# ch559.net
KiCad netlist of a schematic drawn in EAGLE
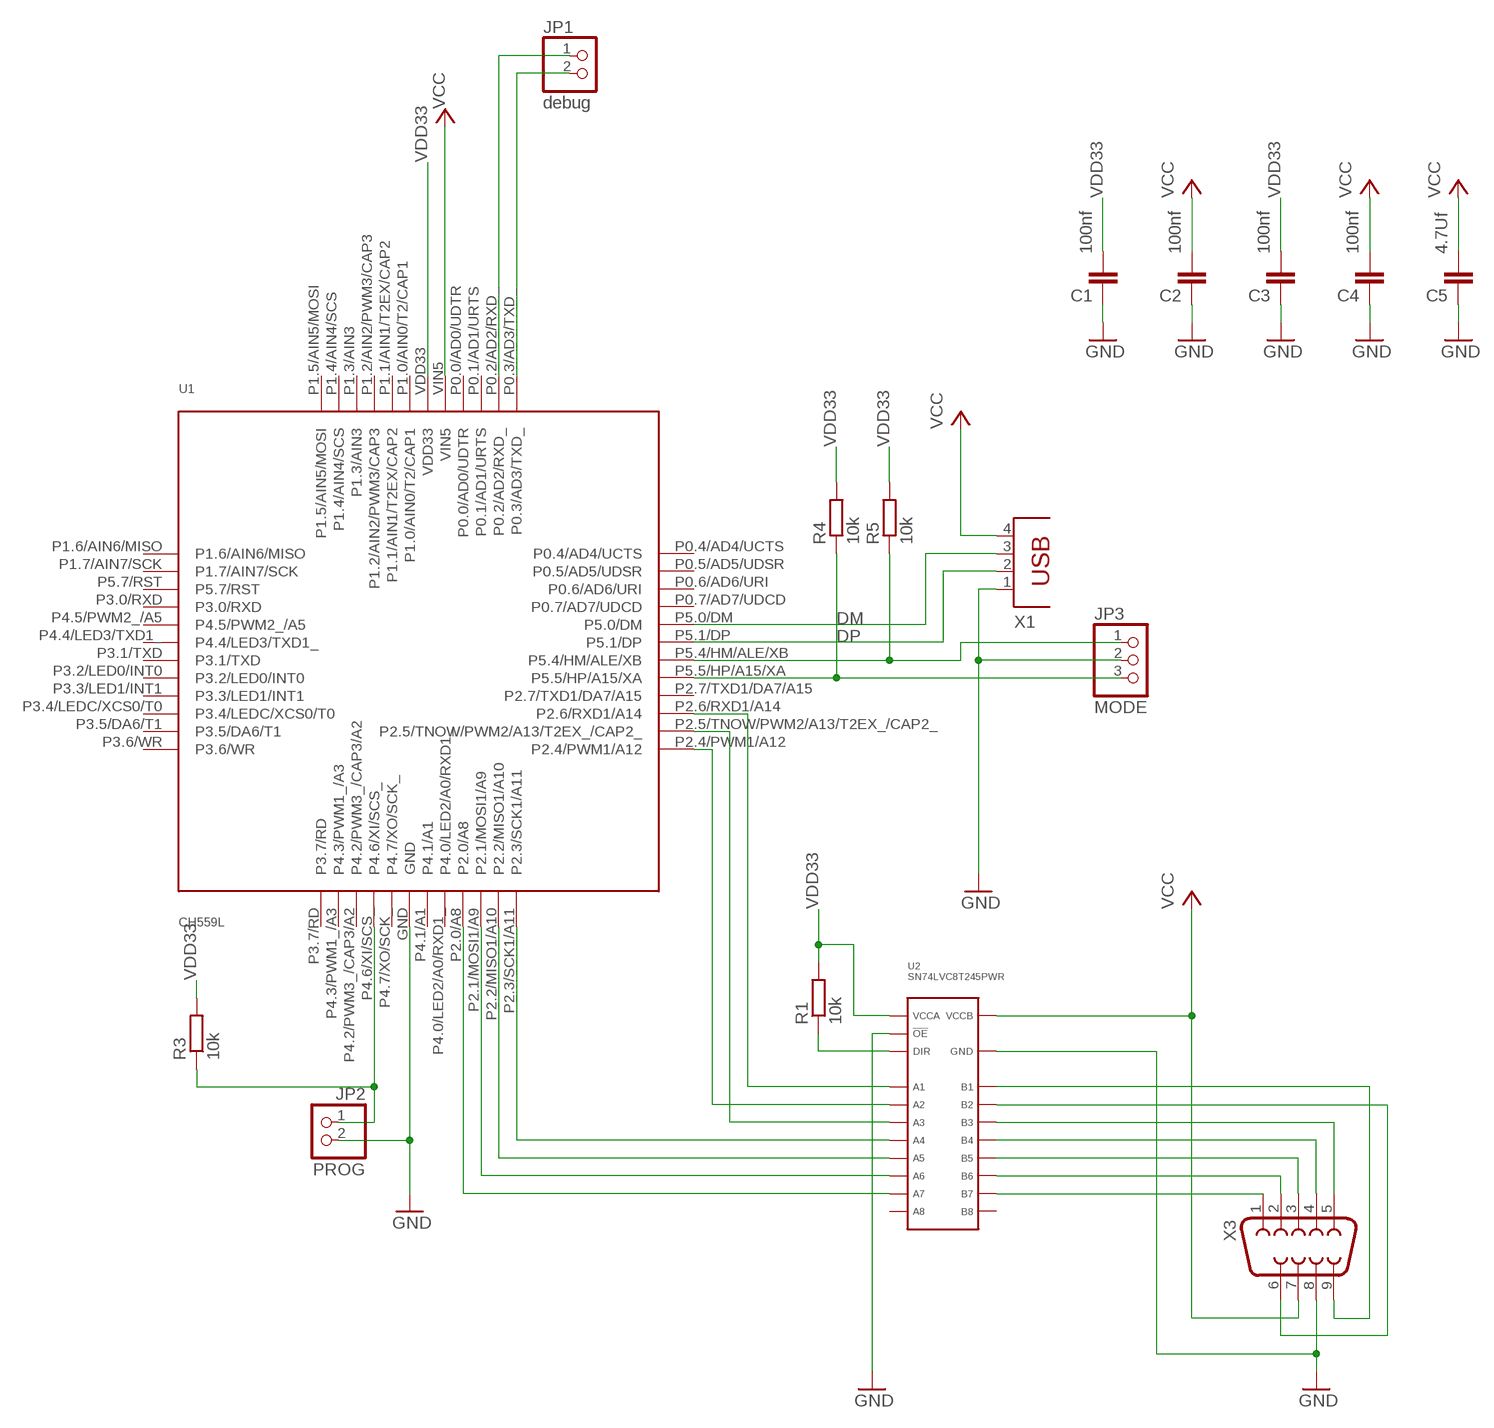
[diagram p0: schematic, sheet 1]

(export (version "E")
  (design (tool "Eeschema 10.0.6"))
  (components
    (comp (ref "C1")
      (value "100nf")
      (footprint "eagle-import:C0603")
      (libsource (lib "eagle-import") (part "C-EUC0603"))
    )
    (comp (ref "C2")
      (value "100nf")
      (footprint "eagle-import:C0603")
      (libsource (lib "eagle-import") (part "C-EUC0603"))
    )
    (comp (ref "C3")
      (value "100nf")
      (footprint "eagle-import:C0603")
      (libsource (lib "eagle-import") (part "C-EUC0603"))
    )
    (comp (ref "C4")
      (value "100nf")
      (footprint "eagle-import:C0603")
      (libsource (lib "eagle-import") (part "C-EUC0603"))
    )
    (comp (ref "C5")
      (value "4.7Uf")
      (footprint "eagle-import:C0603")
      (libsource (lib "eagle-import") (part "C-EUC0603"))
    )
    (comp (ref "JP1")
      (value "debug")
      (footprint "eagle-import:1X02")
      (libsource (lib "eagle-import") (part "pinhead_325_PINHD-1X2"))
    )
    (comp (ref "JP2")
      (value "PROG")
      (footprint "eagle-import:1X02")
      (libsource (lib "eagle-import") (part "PINHD-1X2"))
    )
    (comp (ref "JP3")
      (value "MODE")
      (footprint "eagle-import:1X03")
      (libsource (lib "eagle-import") (part "PINHD-1X3"))
    )
    (comp (ref "R1")
      (value "10k")
      (footprint "eagle-import:R0603")
      (libsource (lib "eagle-import") (part "R-EU_R0603"))
    )
    (comp (ref "R3")
      (value "10k")
      (footprint "eagle-import:R0603")
      (libsource (lib "eagle-import") (part "R-EU_R0603"))
    )
    (comp (ref "R4")
      (value "10k")
      (footprint "eagle-import:R0603")
      (libsource (lib "eagle-import") (part "R-EU_R0603"))
    )
    (comp (ref "R5")
      (value "10k")
      (footprint "eagle-import:R0603")
      (libsource (lib "eagle-import") (part "R-EU_R0603"))
    )
    (comp (ref "U1")
      (value "CH559L")
      (footprint "eagle-import:TQFP48_7X7")
      (libsource (lib "eagle-import") (part "CH559L"))
    )
    (comp (ref "U2")
      (value "SN74LVC8T245PWR")
      (footprint "eagle-import:TTSOP-24")
      (fields (field (name "MF") "Texas Instruments") (field (name "MP") "SN74LVC8T245"))
      (libsource (lib "eagle-import") (part "SN74LVC8T245PWR"))
    )
    (comp (ref "X1")
      (value "PN87520")
      (footprint "eagle-import:PN87520")
      (libsource (lib "eagle-import") (part "PN87520"))
    )
    (comp (ref "X3")
      (value "F09D")
      (footprint "eagle-import:F09D")
      (libsource (lib "eagle-import") (part "F09D"))
    )
  )
  (nets
    (net (code "1") (name "/DM") (class "Default")
      (node (ref "U1") (pin "P5.0/DM") (pinfunction "P5.0/DM_P5.0/DM") (pintype "bidirectional"))
      (node (ref "X1") (pin "3") (pinfunction "3_3") (pintype "passive"))
    )
    (net (code "2") (name "/DP") (class "Default")
      (node (ref "U1") (pin "P5.1/DP") (pinfunction "P5.1/DP_P5.1/DP") (pintype "bidirectional"))
      (node (ref "X1") (pin "2") (pinfunction "2_2") (pintype "passive"))
    )
    (net (code "3") (name "/VDD33") (class "Default")
      (node (ref "C1") (pin "2") (pinfunction "2_2") (pintype "passive"))
      (node (ref "C3") (pin "2") (pinfunction "2_2") (pintype "passive"))
      (node (ref "R1") (pin "2") (pinfunction "2_2") (pintype "passive"))
      (node (ref "R3") (pin "2") (pinfunction "2_2") (pintype "passive"))
      (node (ref "R4") (pin "2") (pinfunction "2_2") (pintype "passive"))
      (node (ref "R5") (pin "2") (pinfunction "2_2") (pintype "passive"))
      (node (ref "U1") (pin "VDD33") (pinfunction "VDD33_VDD33") (pintype "bidirectional"))
      (node (ref "U2") (pin "P$1") (pinfunction "VCCA_P$1") (pintype "bidirectional"))
    )
    (net (code "4") (name "GND") (class "Default")
      (node (ref "C1") (pin "1") (pinfunction "1_1") (pintype "passive"))
      (node (ref "C2") (pin "1") (pinfunction "1_1") (pintype "passive"))
      (node (ref "C3") (pin "1") (pinfunction "1_1") (pintype "passive"))
      (node (ref "C4") (pin "1") (pinfunction "1_1") (pintype "passive"))
      (node (ref "C5") (pin "1") (pinfunction "1_1") (pintype "passive"))
      (node (ref "JP2") (pin "2") (pinfunction "2_2") (pintype "passive"))
      (node (ref "JP3") (pin "2") (pinfunction "2_2") (pintype "passive"))
      (node (ref "U1") (pin "GND") (pinfunction "GND_GND") (pintype "bidirectional"))
      (node (ref "U2") (pin "P$11") (pinfunction "GND_P$11") (pintype "bidirectional"))
      (node (ref "U2") (pin "P$12") (pinfunction "GND_P$12") (pintype "bidirectional"))
      (node (ref "U2") (pin "P$13") (pinfunction "GND_P$13") (pintype "bidirectional"))
      (node (ref "U2") (pin "P$22") (pinfunction "~{OE}_P$22") (pintype "bidirectional"))
      (node (ref "X1") (pin "1") (pinfunction "1_1") (pintype "passive"))
      (node (ref "X3") (pin "8") (pinfunction "8_8") (pintype "passive"))
    )
    (net (code "5") (name "Net-(JP1-Pad1)") (class "Default")
      (node (ref "JP1") (pin "1") (pinfunction "1_1") (pintype "passive"))
      (node (ref "U1") (pin "P0.2/AD2/RXD_") (pinfunction "P0.2/AD2/RXD__P0.2/AD2/RXD_") (pintype "bidirectional"))
    )
    (net (code "6") (name "Net-(JP1-Pad2)") (class "Default")
      (node (ref "JP1") (pin "2") (pinfunction "2_2") (pintype "passive"))
      (node (ref "U1") (pin "P0.3/AD3/TXD_") (pinfunction "P0.3/AD3/TXD__P0.3/AD3/TXD_") (pintype "bidirectional"))
    )
    (net (code "7") (name "Net-(JP2-Pad1)") (class "Default")
      (node (ref "JP2") (pin "1") (pinfunction "1_1") (pintype "passive"))
      (node (ref "R3") (pin "1") (pinfunction "1_1") (pintype "passive"))
      (node (ref "U1") (pin "P4.6/XI/SCS_") (pinfunction "P4.6/XI/SCS__P4.6/XI/SCS_") (pintype "bidirectional"))
    )
    (net (code "8") (name "Net-(JP3-Pad1)") (class "Default")
      (node (ref "JP3") (pin "1") (pinfunction "1_1") (pintype "passive"))
      (node (ref "R5") (pin "1") (pinfunction "1_1") (pintype "passive"))
      (node (ref "U1") (pin "P5.4/HM/ALE/XB") (pinfunction "P5.4/HM/ALE/XB_P5.4/HM/ALE/XB") (pintype "bidirectional"))
    )
    (net (code "9") (name "Net-(JP3-Pad3)") (class "Default")
      (node (ref "JP3") (pin "3") (pinfunction "3_3") (pintype "passive"))
      (node (ref "R4") (pin "1") (pinfunction "1_1") (pintype "passive"))
      (node (ref "U1") (pin "P5.5/HP/A15/XA") (pinfunction "P5.5/HP/A15/XA_P5.5/HP/A15/XA") (pintype "bidirectional"))
    )
    (net (code "10") (name "Net-(U2-A1)") (class "Default")
      (node (ref "U1") (pin "P2.6/RXD1/A14") (pinfunction "P2.6/RXD1/A14_P2.6/RXD1/A14") (pintype "bidirectional"))
      (node (ref "U2") (pin "P$3") (pinfunction "A1_P$3") (pintype "bidirectional"))
    )
    (net (code "11") (name "Net-(U2-A2)") (class "Default")
      (node (ref "U1") (pin "P2.4/PWM1/A12") (pinfunction "P2.4/PWM1/A12_P2.4/PWM1/A12") (pintype "bidirectional"))
      (node (ref "U2") (pin "P$4") (pinfunction "A2_P$4") (pintype "bidirectional"))
    )
    (net (code "12") (name "Net-(U2-A3)") (class "Default")
      (node (ref "U1") (pin "P2.5/TNOW/PWM2/A13/T2EX_/CAP2_") (pinfunction "P2.5/TNOW/PWM2/A13/T2EX_/CAP2__P2.5/TNOW/PWM2/A13/T2EX_/CAP2_") (pintype "bidirectional"))
      (node (ref "U2") (pin "P$5") (pinfunction "A3_P$5") (pintype "bidirectional"))
    )
    (net (code "13") (name "Net-(U2-A4)") (class "Default")
      (node (ref "U1") (pin "P2.3/SCK1/A11") (pinfunction "P2.3/SCK1/A11_P2.3/SCK1/A11") (pintype "bidirectional"))
      (node (ref "U2") (pin "P$6") (pinfunction "A4_P$6") (pintype "bidirectional"))
    )
    (net (code "14") (name "Net-(U2-A5)") (class "Default")
      (node (ref "U1") (pin "P2.2/MISO1/A10") (pinfunction "P2.2/MISO1/A10_P2.2/MISO1/A10") (pintype "bidirectional"))
      (node (ref "U2") (pin "P$7") (pinfunction "A5_P$7") (pintype "bidirectional"))
    )
    (net (code "15") (name "Net-(U2-A6)") (class "Default")
      (node (ref "U1") (pin "P2.1/MOSI1/A9") (pinfunction "P2.1/MOSI1/A9_P2.1/MOSI1/A9") (pintype "bidirectional"))
      (node (ref "U2") (pin "P$8") (pinfunction "A6_P$8") (pintype "bidirectional"))
    )
    (net (code "16") (name "Net-(U2-A7)") (class "Default")
      (node (ref "U1") (pin "P2.0/A8") (pinfunction "P2.0/A8_P2.0/A8") (pintype "bidirectional"))
      (node (ref "U2") (pin "P$9") (pinfunction "A7_P$9") (pintype "bidirectional"))
    )
    (net (code "17") (name "Net-(U2-B1)") (class "Default")
      (node (ref "U2") (pin "P$21") (pinfunction "B1_P$21") (pintype "bidirectional"))
      (node (ref "X3") (pin "9") (pinfunction "9_9") (pintype "passive"))
    )
    (net (code "18") (name "Net-(U2-B2)") (class "Default")
      (node (ref "U2") (pin "P$20") (pinfunction "B2_P$20") (pintype "bidirectional"))
      (node (ref "X3") (pin "6") (pinfunction "6_6") (pintype "passive"))
    )
    (net (code "19") (name "Net-(U2-B3)") (class "Default")
      (node (ref "U2") (pin "P$19") (pinfunction "B3_P$19") (pintype "bidirectional"))
      (node (ref "X3") (pin "5") (pinfunction "5_5") (pintype "passive"))
    )
    (net (code "20") (name "Net-(U2-B4)") (class "Default")
      (node (ref "U2") (pin "P$18") (pinfunction "B4_P$18") (pintype "bidirectional"))
      (node (ref "X3") (pin "4") (pinfunction "4_4") (pintype "passive"))
    )
    (net (code "21") (name "Net-(U2-B5)") (class "Default")
      (node (ref "U2") (pin "P$17") (pinfunction "B5_P$17") (pintype "bidirectional"))
      (node (ref "X3") (pin "3") (pinfunction "3_3") (pintype "passive"))
    )
    (net (code "22") (name "Net-(U2-B6)") (class "Default")
      (node (ref "U2") (pin "P$16") (pinfunction "B6_P$16") (pintype "bidirectional"))
      (node (ref "X3") (pin "2") (pinfunction "2_2") (pintype "passive"))
    )
    (net (code "23") (name "Net-(U2-B7)") (class "Default")
      (node (ref "U2") (pin "P$15") (pinfunction "B7_P$15") (pintype "bidirectional"))
      (node (ref "X3") (pin "1") (pinfunction "1_1") (pintype "passive"))
    )
    (net (code "24") (name "Net-(U2-DIR)") (class "Default")
      (node (ref "R1") (pin "1") (pinfunction "1_1") (pintype "passive"))
      (node (ref "U2") (pin "P$2") (pinfunction "DIR_P$2") (pintype "bidirectional"))
    )
    (net (code "25") (name "VCC") (class "Default")
      (node (ref "C2") (pin "2") (pinfunction "2_2") (pintype "passive"))
      (node (ref "C4") (pin "2") (pinfunction "2_2") (pintype "passive"))
      (node (ref "C5") (pin "2") (pinfunction "2_2") (pintype "passive"))
      (node (ref "U1") (pin "VIN5") (pinfunction "VIN5_VIN5") (pintype "bidirectional"))
      (node (ref "U2") (pin "P$23") (pinfunction "VCCB_P$23") (pintype "bidirectional"))
      (node (ref "U2") (pin "P$24") (pinfunction "VCCB_P$24") (pintype "bidirectional"))
      (node (ref "X1") (pin "4") (pinfunction "4_4") (pintype "passive"))
      (node (ref "X3") (pin "7") (pinfunction "7_7") (pintype "passive"))
    )
    (net (code "26") (name "unconnected-(U1-PadP0.0{slash}AD0{slash}UDTR)") (class "Default")
      (node (ref "U1") (pin "P0.0/AD0/UDTR") (pinfunction "P0.0/AD0/UDTR_P0.0/AD0/UDTR") (pintype "bidirectional"))
    )
    (net (code "27") (name "unconnected-(U1-PadP0.1{slash}AD1{slash}URTS)") (class "Default")
      (node (ref "U1") (pin "P0.1/AD1/URTS") (pinfunction "P0.1/AD1/URTS_P0.1/AD1/URTS") (pintype "bidirectional"))
    )
    (net (code "28") (name "unconnected-(U1-PadP0.4{slash}AD4{slash}UCTS)") (class "Default")
      (node (ref "U1") (pin "P0.4/AD4/UCTS") (pinfunction "P0.4/AD4/UCTS_P0.4/AD4/UCTS") (pintype "bidirectional"))
    )
    (net (code "29") (name "unconnected-(U1-PadP0.5{slash}AD5{slash}UDSR)") (class "Default")
      (node (ref "U1") (pin "P0.5/AD5/UDSR") (pinfunction "P0.5/AD5/UDSR_P0.5/AD5/UDSR") (pintype "bidirectional"))
    )
    (net (code "30") (name "unconnected-(U1-PadP0.6{slash}AD6{slash}URI)") (class "Default")
      (node (ref "U1") (pin "P0.6/AD6/URI") (pinfunction "P0.6/AD6/URI_P0.6/AD6/URI") (pintype "bidirectional"))
    )
    (net (code "31") (name "unconnected-(U1-PadP0.7{slash}AD7{slash}UDCD)") (class "Default")
      (node (ref "U1") (pin "P0.7/AD7/UDCD") (pinfunction "P0.7/AD7/UDCD_P0.7/AD7/UDCD") (pintype "bidirectional"))
    )
    (net (code "32") (name "unconnected-(U1-PadP1.0{slash}AIN0{slash}T2{slash}CAP1)") (class "Default")
      (node (ref "U1") (pin "P1.0/AIN0/T2/CAP1") (pinfunction "P1.0/AIN0/T2/CAP1_P1.0/AIN0/T2/CAP1") (pintype "bidirectional"))
    )
    (net (code "33") (name "unconnected-(U1-PadP1.1{slash}AIN1{slash}T2EX{slash}CAP2)") (class "Default")
      (node (ref "U1") (pin "P1.1/AIN1/T2EX/CAP2") (pinfunction "P1.1/AIN1/T2EX/CAP2_P1.1/AIN1/T2EX/CAP2") (pintype "bidirectional"))
    )
    (net (code "34") (name "unconnected-(U1-PadP1.2{slash}AIN2{slash}PWM3{slash}CAP3)") (class "Default")
      (node (ref "U1") (pin "P1.2/AIN2/PWM3/CAP3") (pinfunction "P1.2/AIN2/PWM3/CAP3_P1.2/AIN2/PWM3/CAP3") (pintype "bidirectional"))
    )
    (net (code "35") (name "unconnected-(U1-PadP1.3{slash}AIN3)") (class "Default")
      (node (ref "U1") (pin "P1.3/AIN3") (pinfunction "P1.3/AIN3_P1.3/AIN3") (pintype "bidirectional"))
    )
    (net (code "36") (name "unconnected-(U1-PadP1.4{slash}AIN4{slash}SCS)") (class "Default")
      (node (ref "U1") (pin "P1.4/AIN4/SCS") (pinfunction "P1.4/AIN4/SCS_P1.4/AIN4/SCS") (pintype "bidirectional"))
    )
    (net (code "37") (name "unconnected-(U1-PadP1.5{slash}AIN5{slash}MOSI)") (class "Default")
      (node (ref "U1") (pin "P1.5/AIN5/MOSI") (pinfunction "P1.5/AIN5/MOSI_P1.5/AIN5/MOSI") (pintype "bidirectional"))
    )
    (net (code "38") (name "unconnected-(U1-PadP1.6{slash}AIN6{slash}MISO)") (class "Default")
      (node (ref "U1") (pin "P1.6/AIN6/MISO") (pinfunction "P1.6/AIN6/MISO_P1.6/AIN6/MISO") (pintype "bidirectional"))
    )
    (net (code "39") (name "unconnected-(U1-PadP1.7{slash}AIN7{slash}SCK)") (class "Default")
      (node (ref "U1") (pin "P1.7/AIN7/SCK") (pinfunction "P1.7/AIN7/SCK_P1.7/AIN7/SCK") (pintype "bidirectional"))
    )
    (net (code "40") (name "unconnected-(U1-PadP2.7{slash}TXD1{slash}DA7{slash}A15)") (class "Default")
      (node (ref "U1") (pin "P2.7/TXD1/DA7/A15") (pinfunction "P2.7/TXD1/DA7/A15_P2.7/TXD1/DA7/A15") (pintype "bidirectional"))
    )
    (net (code "41") (name "unconnected-(U1-PadP3.0{slash}RXD)") (class "Default")
      (node (ref "U1") (pin "P3.0/RXD") (pinfunction "P3.0/RXD_P3.0/RXD") (pintype "bidirectional"))
    )
    (net (code "42") (name "unconnected-(U1-PadP3.1{slash}TXD)") (class "Default")
      (node (ref "U1") (pin "P3.1/TXD") (pinfunction "P3.1/TXD_P3.1/TXD") (pintype "bidirectional"))
    )
    (net (code "43") (name "unconnected-(U1-PadP3.2{slash}LED0{slash}INT0)") (class "Default")
      (node (ref "U1") (pin "P3.2/LED0/INT0") (pinfunction "P3.2/LED0/INT0_P3.2/LED0/INT0") (pintype "bidirectional"))
    )
    (net (code "44") (name "unconnected-(U1-PadP3.3{slash}LED1{slash}INT1)") (class "Default")
      (node (ref "U1") (pin "P3.3/LED1/INT1") (pinfunction "P3.3/LED1/INT1_P3.3/LED1/INT1") (pintype "bidirectional"))
    )
    (net (code "45") (name "unconnected-(U1-PadP3.4{slash}LEDC{slash}XCS0{slash}T0)") (class "Default")
      (node (ref "U1") (pin "P3.4/LEDC/XCS0/T0") (pinfunction "P3.4/LEDC/XCS0/T0_P3.4/LEDC/XCS0/T0") (pintype "bidirectional"))
    )
    (net (code "46") (name "unconnected-(U1-PadP3.5{slash}DA6{slash}T1)") (class "Default")
      (node (ref "U1") (pin "P3.5/DA6/T1") (pinfunction "P3.5/DA6/T1_P3.5/DA6/T1") (pintype "bidirectional"))
    )
    (net (code "47") (name "unconnected-(U1-PadP3.6{slash}WR)") (class "Default")
      (node (ref "U1") (pin "P3.6/WR") (pinfunction "P3.6/WR_P3.6/WR") (pintype "bidirectional"))
    )
    (net (code "48") (name "unconnected-(U1-PadP3.7{slash}RD)") (class "Default")
      (node (ref "U1") (pin "P3.7/RD") (pinfunction "P3.7/RD_P3.7/RD") (pintype "bidirectional"))
    )
    (net (code "49") (name "unconnected-(U1-PadP4.0{slash}LED2{slash}A0{slash}RXD1_)") (class "Default")
      (node (ref "U1") (pin "P4.0/LED2/A0/RXD1_") (pinfunction "P4.0/LED2/A0/RXD1__P4.0/LED2/A0/RXD1_") (pintype "bidirectional"))
    )
    (net (code "50") (name "unconnected-(U1-PadP4.1{slash}A1)") (class "Default")
      (node (ref "U1") (pin "P4.1/A1") (pinfunction "P4.1/A1_P4.1/A1") (pintype "bidirectional"))
    )
    (net (code "51") (name "unconnected-(U1-PadP4.2{slash}PWM3_{slash}CAP3{slash}A2)") (class "Default")
      (node (ref "U1") (pin "P4.2/PWM3_/CAP3/A2") (pinfunction "P4.2/PWM3_/CAP3/A2_P4.2/PWM3_/CAP3/A2") (pintype "bidirectional"))
    )
    (net (code "52") (name "unconnected-(U1-PadP4.3{slash}PWM1_{slash}A3)") (class "Default")
      (node (ref "U1") (pin "P4.3/PWM1_/A3") (pinfunction "P4.3/PWM1_/A3_P4.3/PWM1_/A3") (pintype "bidirectional"))
    )
    (net (code "53") (name "unconnected-(U1-PadP4.4{slash}LED3{slash}TXD1_)") (class "Default")
      (node (ref "U1") (pin "P4.4/LED3/TXD1_") (pinfunction "P4.4/LED3/TXD1__P4.4/LED3/TXD1_") (pintype "bidirectional"))
    )
    (net (code "54") (name "unconnected-(U1-PadP4.5{slash}PWM2_{slash}A5)") (class "Default")
      (node (ref "U1") (pin "P4.5/PWM2_/A5") (pinfunction "P4.5/PWM2_/A5_P4.5/PWM2_/A5") (pintype "bidirectional"))
    )
    (net (code "55") (name "unconnected-(U1-PadP4.7{slash}XO{slash}SCK_)") (class "Default")
      (node (ref "U1") (pin "P4.7/XO/SCK_") (pinfunction "P4.7/XO/SCK__P4.7/XO/SCK_") (pintype "bidirectional"))
    )
    (net (code "56") (name "unconnected-(U1-PadP5.7{slash}RST)") (class "Default")
      (node (ref "U1") (pin "P5.7/RST") (pinfunction "P5.7/RST_P5.7/RST") (pintype "bidirectional"))
    )
    (net (code "57") (name "unconnected-(U2-A8-PadP$10)") (class "Default")
      (node (ref "U2") (pin "P$10") (pinfunction "A8_P$10") (pintype "bidirectional"))
    )
    (net (code "58") (name "unconnected-(U2-B8-PadP$14)") (class "Default")
      (node (ref "U2") (pin "P$14") (pinfunction "B8_P$14") (pintype "bidirectional"))
    )
  )
)
